# LPC8N04demoVB.net
KiCad netlist of a schematic drawn in Altium Designer
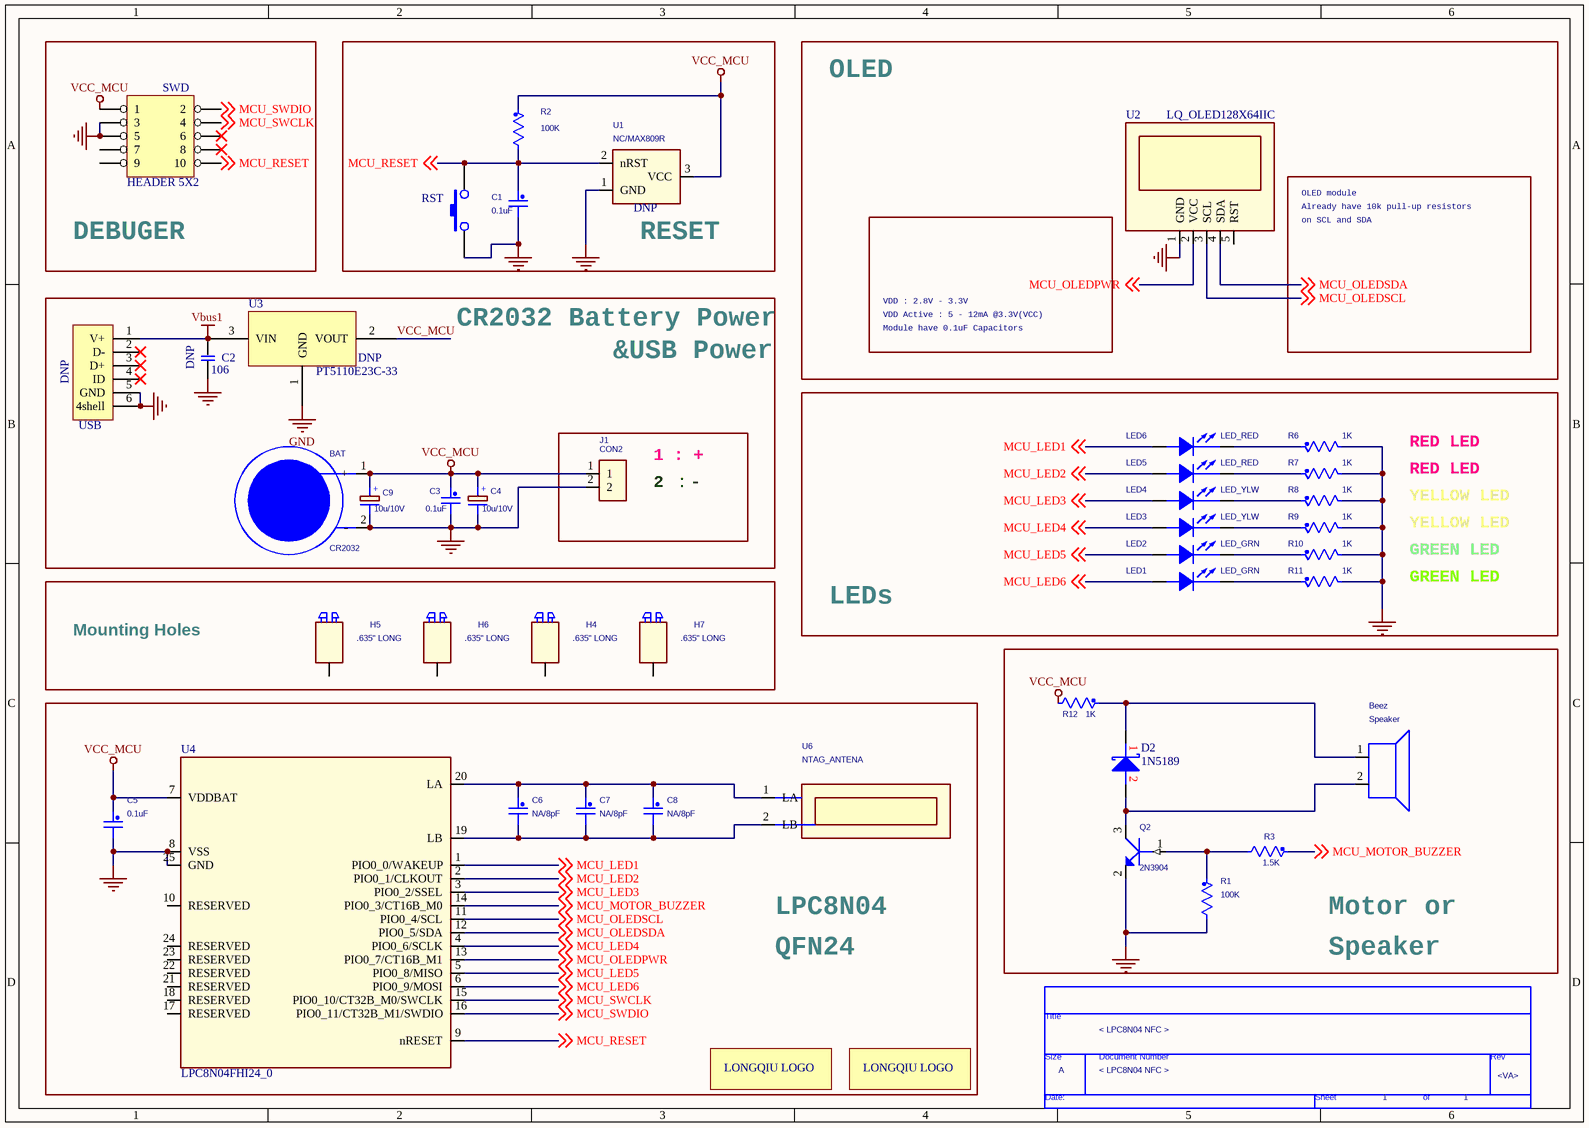
[diagram p0: LPC8N04demoVB.SchDoc]

(export (version "E")
  (design (tool "Eeschema 10.0.6"))
  (components
    (comp (ref "*")
      (value "TitleBlock0")
      (fields
        (field (name "DOC") "< LPC8N04 NFC >")
        (field (name "REVCODE") "<VA>")
        (field (name "TITLE") "< LPC8N04 NFC >")
        (field (name "PAGE SIZE") "A")
        (field (name "PAGE NUMBER") "1")
        (field (name "PAGE COUNT") "1")
      )
      (libsource (lib "*") (part "TitleBlock0"))
    )
    (comp (ref "BAT") (value "CR2032") (footprint "LQ_CR2032") (libsource (lib "*") (part "CR2032")))
    (comp (ref "Beez") (value "Speaker") (libsource (lib "*") (part "BUZZER_0")))
    (comp (ref "C1") (value "0.1uF") (footprint "LQ_C0603") (libsource (lib "*") (part "C_Generic")))
    (comp (ref "C2")
      (value "106")
      (footprint "LQ_C1206T")
      (description "CAP")
      (libsource (lib "*") (part "LQ_CAP"))
    )
    (comp (ref "C3") (value "0.1uF") (footprint "LQ_C0603") (libsource (lib "*") (part "C_Generic")))
    (comp (ref "C4") (value "10u/10V") (libsource (lib "*") (part "CAP PN")))
    (comp (ref "C5") (value "0.1uF") (footprint "LQ_C0603") (libsource (lib "*") (part "C_Generic")))
    (comp (ref "C6") (value "NA/8pF") (footprint "LQ_C0603") (libsource (lib "*") (part "C_Generic")))
    (comp (ref "C7") (value "NA/8pF") (footprint "LQ_C0603") (libsource (lib "*") (part "C_Generic")))
    (comp (ref "C8") (value "NA/8pF") (footprint "LQ_C0603") (libsource (lib "*") (part "C_Generic")))
    (comp (ref "C9") (value "10u/10V") (libsource (lib "*") (part "CAP PN")))
    (comp (ref "D2")
      (value "1N5189")
      (footprint "LQ_D1206Z")
      (description "Schottky Diode")
      (libsource (lib "chiusir") (part "LQ_Z"))
    )
    (comp (ref "H4")
      (value ".635\" LONG")
      (description "FASTENER, STANDOFF 4.5MMX3.53XM3.0X0.5 ROUND THR .635\"L BRASS")
      (libsource (lib "*") (part "SPACER"))
    )
    (comp (ref "H5")
      (value ".635\" LONG")
      (description "FASTENER, STANDOFF 4.5MMX3.53XM3.0X0.5 ROUND THR .635\"L BRASS")
      (libsource (lib "*") (part "SPACER"))
    )
    (comp (ref "H6")
      (value ".635\" LONG")
      (description "FASTENER, STANDOFF 4.5MMX3.53XM3.0X0.5 ROUND THR .635\"L BRASS")
      (libsource (lib "*") (part "SPACER"))
    )
    (comp (ref "H7")
      (value ".635\" LONG")
      (description "FASTENER, STANDOFF 4.5MMX3.53XM3.0X0.5 ROUND THR .635\"L BRASS")
      (libsource (lib "*") (part "SPACER"))
    )
    (comp (ref "J1") (value "CON2") (footprint "LQ_SIP2") (libsource (lib "*") (part "CON2")))
    (comp (ref "LED1") (value "LED_GRN") (libsource (lib "*") (part "LED_DIP_0")))
    (comp (ref "LED2") (value "LED_GRN") (libsource (lib "*") (part "LED_DIP_0")))
    (comp (ref "LED3") (value "LED_YLW") (libsource (lib "*") (part "LED_DIP_0")))
    (comp (ref "LED4") (value "LED_YLW") (libsource (lib "*") (part "LED_DIP_0")))
    (comp (ref "LED5") (value "LED_RED") (libsource (lib "*") (part "LED_DIP_0")))
    (comp (ref "LED6") (value "LED_RED") (libsource (lib "*") (part "LED_DIP_0")))
    (comp (ref "LQ") (value "LOGO") (footprint "LOGO5X8MM") (libsource (lib "chiusir") (part "LOGO")))
    (comp (ref "LQ1") (value "LOGO") (footprint "NXPlogo35X81mm") (libsource (lib "chiusir") (part "LOGO")))
    (comp (ref "Q2") (value "2N3904") (libsource (lib "*") (part "2N3904_0")))
    (comp (ref "R1") (value "100K") (footprint "LQ_R0603") (libsource (lib "*") (part "Register")))
    (comp (ref "R2") (value "100K") (libsource (lib "*") (part "R_Generic")))
    (comp (ref "R3") (value "1.5K") (footprint "LQ_R0603") (libsource (lib "*") (part "Register")))
    (comp (ref "R6") (value "1K") (footprint "LQ_R0603") (libsource (lib "*") (part "Register_Dup1")))
    (comp (ref "R7") (value "1K") (footprint "LQ_R0603") (libsource (lib "*") (part "Register_Dup1")))
    (comp (ref "R8") (value "1K") (footprint "LQ_R0603") (libsource (lib "*") (part "Register_Dup1")))
    (comp (ref "R9") (value "1K") (footprint "LQ_R0603") (libsource (lib "*") (part "Register_Dup1")))
    (comp (ref "R10") (value "1K") (footprint "LQ_R0603") (libsource (lib "*") (part "Register_Dup1")))
    (comp (ref "R11") (value "1K") (footprint "LQ_R0603") (libsource (lib "*") (part "Register_Dup1")))
    (comp (ref "R12") (value "1K") (footprint "LQ_R0603") (libsource (lib "*") (part "Register")))
    (comp (ref "RST") (value "SW-PB") (footprint "LQ_BT2SMT") (libsource (lib "*") (part "SW-PB")))
    (comp (ref "SWD")
      (value "HEADER 5X2")
      (footprint "LQ_JTAG5X2-1.27")
      (libsource (lib "*") (part "HEADER 5X2"))
    )
    (comp (ref "U1") (value "NC/MAX809R") (footprint "LQ_SOT-23NPN") (libsource (lib "*") (part "MAX809R")))
    (comp (ref "U2")
      (value "LQ_OLED128X64IIC")
      (footprint "LQ_OLED128x64IIC")
      (libsource (lib "LPC8N04_CLOCK_162_Library") (part "LQ_OLED128645IIC"))
    )
    (comp (ref "U3")
      (value "PT5110E23C-33")
      (footprint "LQ_SOT-23NPN")
      (libsource (lib "ForMyUse") (part "AMS1117"))
    )
    (comp (ref "U4")
      (value "LPC8N04FHI24_0")
      (footprint "LQ_HVQFN24")
      (libsource (lib "LPC8N04_CLOCK_162_Library") (part "LPC8N04FHI24_0"))
    )
    (comp (ref "U6")
      (value "NTAG_ANTENA")
      (footprint "NFCClass3Ant3T-2")
      (libsource (lib "*") (part "NTAG_ANTENA"))
    )
    (comp (ref "USB") (value "USB") (footprint "LQ_MICROUSB-5PIN") (libsource (lib "*") (part "MINIUSB")))
  )
  (nets
    (net (code "1") (name "GND") (class "Default")
      (node (ref "BAT") (pin "2") (pinfunction "-_2") (pintype "passive"))
      (node (ref "C1") (pin "2") (pinfunction "2_2") (pintype "passive"))
      (node (ref "C2") (pin "2") (pinfunction "2_2") (pintype "passive"))
      (node (ref "C3") (pin "2") (pinfunction "2_2") (pintype "passive"))
      (node (ref "C4") (pin "2") (pinfunction "2_2") (pintype "passive"))
      (node (ref "C5") (pin "2") (pinfunction "2_2") (pintype "passive"))
      (node (ref "C9") (pin "2") (pinfunction "2_2") (pintype "passive"))
      (node (ref "J1") (pin "2") (pinfunction "2_2") (pintype "passive"))
      (node (ref "Q2") (pin "2") (pinfunction "EMITTER_2") (pintype "passive"))
      (node (ref "R1") (pin "2") (pinfunction "2_2") (pintype "passive"))
      (node (ref "R10") (pin "2") (pinfunction "2_2") (pintype "passive"))
      (node (ref "R11") (pin "2") (pinfunction "2_2") (pintype "passive"))
      (node (ref "R6") (pin "2") (pinfunction "2_2") (pintype "passive"))
      (node (ref "R7") (pin "2") (pinfunction "2_2") (pintype "passive"))
      (node (ref "R8") (pin "2") (pinfunction "2_2") (pintype "passive"))
      (node (ref "R9") (pin "2") (pinfunction "2_2") (pintype "passive"))
      (node (ref "RST") (pin "1") (pinfunction "1_1") (pintype "passive"))
      (node (ref "SWD") (pin "3") (pinfunction "3_3") (pintype "passive"))
      (node (ref "SWD") (pin "5") (pinfunction "5_5") (pintype "passive"))
      (node (ref "U1") (pin "1") (pinfunction "GND_1") (pintype "passive"))
      (node (ref "U2") (pin "1") (pinfunction "GND_1") (pintype "passive"))
      (node (ref "U3") (pin "1") (pinfunction "GND_1") (pintype "power_in"))
      (node (ref "U4") (pin "25") (pinfunction "GND_25") (pintype "passive"))
      (node (ref "U4") (pin "8") (pinfunction "VSS_8") (pintype "passive"))
      (node (ref "USB") (pin "5") (pinfunction "GND_5") (pintype "passive"))
      (node (ref "USB") (pin "6") (pinfunction "4shell_6") (pintype "passive"))
    )
    (net (code "2") (name "MCU_LED1") (class "Default")
      (node (ref "LED6") (pin "1") (pinfunction "ANODE_1") (pintype "passive"))
      (node (ref "U4") (pin "1") (pinfunction "PIO0_0/WAKEUP_1") (pintype "passive"))
    )
    (net (code "3") (name "MCU_LED2") (class "Default")
      (node (ref "LED5") (pin "1") (pinfunction "ANODE_1") (pintype "passive"))
      (node (ref "U4") (pin "2") (pinfunction "PIO0_1/CLKOUT_2") (pintype "passive"))
    )
    (net (code "4") (name "MCU_LED3") (class "Default")
      (node (ref "LED4") (pin "1") (pinfunction "ANODE_1") (pintype "passive"))
      (node (ref "U4") (pin "3") (pinfunction "PIO0_2/SSEL_3") (pintype "passive"))
    )
    (net (code "5") (name "MCU_LED4") (class "Default")
      (node (ref "LED3") (pin "1") (pinfunction "ANODE_1") (pintype "passive"))
      (node (ref "U4") (pin "4") (pinfunction "PIO0_6/SCLK_4") (pintype "passive"))
    )
    (net (code "6") (name "MCU_LED5") (class "Default")
      (node (ref "LED2") (pin "1") (pinfunction "ANODE_1") (pintype "passive"))
      (node (ref "U4") (pin "5") (pinfunction "PIO0_8/MISO_5") (pintype "passive"))
    )
    (net (code "7") (name "MCU_LED6") (class "Default")
      (node (ref "LED1") (pin "1") (pinfunction "ANODE_1") (pintype "passive"))
      (node (ref "U4") (pin "6") (pinfunction "PIO0_9/MOSI_6") (pintype "passive"))
    )
    (net (code "8") (name "MCU_MOTOR_BUZZER") (class "Default")
      (node (ref "R3") (pin "1") (pinfunction "1_1") (pintype "passive"))
      (node (ref "U4") (pin "14") (pinfunction "PIO0_3/CT16B_M0_14") (pintype "passive"))
    )
    (net (code "9") (name "MCU_OLEDPWR") (class "Default")
      (node (ref "U2") (pin "2") (pinfunction "VCC_2") (pintype "passive"))
      (node (ref "U4") (pin "13") (pinfunction "PIO0_7/CT16B_M1_13") (pintype "passive"))
    )
    (net (code "10") (name "MCU_OLEDSCL") (class "Default")
      (node (ref "U2") (pin "3") (pinfunction "SCL_3") (pintype "passive"))
      (node (ref "U4") (pin "11") (pinfunction "PIO0_4/SCL_11") (pintype "passive"))
    )
    (net (code "11") (name "MCU_OLEDSDA") (class "Default")
      (node (ref "U2") (pin "4") (pinfunction "SDA_4") (pintype "passive"))
      (node (ref "U4") (pin "12") (pinfunction "PIO0_5/SDA_12") (pintype "passive"))
    )
    (net (code "12") (name "MCU_RESET") (class "Default")
      (node (ref "C1") (pin "1") (pinfunction "1_1") (pintype "passive"))
      (node (ref "R2") (pin "2") (pinfunction "2_2") (pintype "passive"))
      (node (ref "RST") (pin "2") (pinfunction "2_2") (pintype "passive"))
      (node (ref "SWD") (pin "10") (pinfunction "10_10") (pintype "passive"))
      (node (ref "U1") (pin "2") (pinfunction "nRST_2") (pintype "passive"))
      (node (ref "U4") (pin "9") (pinfunction "nRESET_9") (pintype "passive"))
    )
    (net (code "13") (name "MCU_SWCLK") (class "Default")
      (node (ref "SWD") (pin "4") (pinfunction "4_4") (pintype "passive"))
      (node (ref "U4") (pin "15") (pinfunction "PIO0_10/CT32B_M0/SWCLK_15") (pintype "passive"))
    )
    (net (code "14") (name "MCU_SWDIO") (class "Default")
      (node (ref "SWD") (pin "2") (pinfunction "2_2") (pintype "passive"))
      (node (ref "U4") (pin "16") (pinfunction "PIO0_11/CT32B_M1/SWDIO_16") (pintype "passive"))
    )
    (net (code "15") (name "Net-(Beez-A)") (class "Default")
      (node (ref "Beez") (pin "1") (pinfunction "A_1") (pintype "passive"))
      (node (ref "D2") (pin "1") (pinfunction "1_1") (pintype "passive"))
      (node (ref "R12") (pin "1") (pinfunction "1_1") (pintype "passive"))
    )
    (net (code "16") (name "Net-(Beez-B)") (class "Default")
      (node (ref "Beez") (pin "2") (pinfunction "B_2") (pintype "passive"))
      (node (ref "D2") (pin "2") (pinfunction "2_2") (pintype "passive"))
      (node (ref "Q2") (pin "3") (pinfunction "COLLECTOR_3") (pintype "passive"))
    )
    (net (code "17") (name "Net-(LED1-CATHODE)") (class "Default")
      (node (ref "LED1") (pin "2") (pinfunction "CATHODE_2") (pintype "passive"))
      (node (ref "R11") (pin "1") (pinfunction "1_1") (pintype "passive"))
    )
    (net (code "18") (name "Net-(LED2-CATHODE)") (class "Default")
      (node (ref "LED2") (pin "2") (pinfunction "CATHODE_2") (pintype "passive"))
      (node (ref "R10") (pin "1") (pinfunction "1_1") (pintype "passive"))
    )
    (net (code "19") (name "Net-(LED3-CATHODE)") (class "Default")
      (node (ref "LED3") (pin "2") (pinfunction "CATHODE_2") (pintype "passive"))
      (node (ref "R9") (pin "1") (pinfunction "1_1") (pintype "passive"))
    )
    (net (code "20") (name "Net-(LED4-CATHODE)") (class "Default")
      (node (ref "LED4") (pin "2") (pinfunction "CATHODE_2") (pintype "passive"))
      (node (ref "R8") (pin "1") (pinfunction "1_1") (pintype "passive"))
    )
    (net (code "21") (name "Net-(LED5-CATHODE)") (class "Default")
      (node (ref "LED5") (pin "2") (pinfunction "CATHODE_2") (pintype "passive"))
      (node (ref "R7") (pin "1") (pinfunction "1_1") (pintype "passive"))
    )
    (net (code "22") (name "Net-(LED6-CATHODE)") (class "Default")
      (node (ref "LED6") (pin "2") (pinfunction "CATHODE_2") (pintype "passive"))
      (node (ref "R6") (pin "1") (pinfunction "1_1") (pintype "passive"))
    )
    (net (code "23") (name "Net-(Q2-BASE)") (class "Default")
      (node (ref "Q2") (pin "1") (pinfunction "BASE_1") (pintype "input"))
      (node (ref "R1") (pin "1") (pinfunction "1_1") (pintype "passive"))
      (node (ref "R3") (pin "2") (pinfunction "2_2") (pintype "passive"))
    )
    (net (code "24") (name "Net-(U4-LA)") (class "Default")
      (node (ref "C6") (pin "1") (pinfunction "1_1") (pintype "passive"))
      (node (ref "C7") (pin "1") (pinfunction "1_1") (pintype "passive"))
      (node (ref "C8") (pin "1") (pinfunction "1_1") (pintype "passive"))
      (node (ref "U4") (pin "20") (pinfunction "LA_20") (pintype "passive"))
      (node (ref "U6") (pin "1") (pinfunction "LA_1") (pintype "passive"))
    )
    (net (code "25") (name "Net-(U4-LB)") (class "Default")
      (node (ref "C6") (pin "2") (pinfunction "2_2") (pintype "passive"))
      (node (ref "C7") (pin "2") (pinfunction "2_2") (pintype "passive"))
      (node (ref "C8") (pin "2") (pinfunction "2_2") (pintype "passive"))
      (node (ref "U4") (pin "19") (pinfunction "LB_19") (pintype "passive"))
      (node (ref "U6") (pin "2") (pinfunction "LB_2") (pintype "passive"))
    )
    (net (code "26") (name "VCC_MCU") (class "Default")
      (node (ref "BAT") (pin "1") (pinfunction "+_1") (pintype "passive"))
      (node (ref "C3") (pin "1") (pinfunction "1_1") (pintype "passive"))
      (node (ref "C4") (pin "1") (pinfunction "1_1") (pintype "passive"))
      (node (ref "C5") (pin "1") (pinfunction "1_1") (pintype "passive"))
      (node (ref "C9") (pin "1") (pinfunction "1_1") (pintype "passive"))
      (node (ref "J1") (pin "1") (pinfunction "1_1") (pintype "passive"))
      (node (ref "R12") (pin "2") (pinfunction "2_2") (pintype "passive"))
      (node (ref "R2") (pin "1") (pinfunction "1_1") (pintype "passive"))
      (node (ref "SWD") (pin "1") (pinfunction "1_1") (pintype "passive"))
      (node (ref "U1") (pin "3") (pinfunction "VCC_3") (pintype "passive"))
      (node (ref "U3") (pin "2") (pinfunction "VOUT_2") (pintype "power_in"))
      (node (ref "U4") (pin "7") (pinfunction "VDDBAT_7") (pintype "passive"))
    )
    (net (code "27") (name "Vbus1") (class "Default")
      (node (ref "C2") (pin "1") (pinfunction "1_1") (pintype "passive"))
      (node (ref "U3") (pin "3") (pinfunction "VIN_3") (pintype "power_in"))
      (node (ref "USB") (pin "1") (pinfunction "V+_1") (pintype "passive"))
    )
    (net (code "28") (name "unconnected-(H4-NC_1-Pad1)") (class "Default")
      (node (ref "H4") (pin "1") (pinfunction "NC_1_1") (pintype "passive"))
    )
    (net (code "29") (name "unconnected-(H5-NC_1-Pad1)") (class "Default")
      (node (ref "H5") (pin "1") (pinfunction "NC_1_1") (pintype "passive"))
    )
    (net (code "30") (name "unconnected-(H6-NC_1-Pad1)") (class "Default")
      (node (ref "H6") (pin "1") (pinfunction "NC_1_1") (pintype "passive"))
    )
    (net (code "31") (name "unconnected-(H7-NC_1-Pad1)") (class "Default")
      (node (ref "H7") (pin "1") (pinfunction "NC_1_1") (pintype "passive"))
    )
    (net (code "32") (name "unconnected-(SWD-Pad6)") (class "Default")
      (node (ref "SWD") (pin "6") (pinfunction "6_6") (pintype "passive+no_connect"))
    )
    (net (code "33") (name "unconnected-(SWD-Pad7)") (class "Default")
      (node (ref "SWD") (pin "7") (pinfunction "7_7") (pintype "passive"))
    )
    (net (code "34") (name "unconnected-(SWD-Pad8)") (class "Default")
      (node (ref "SWD") (pin "8") (pinfunction "8_8") (pintype "passive+no_connect"))
    )
    (net (code "35") (name "unconnected-(SWD-Pad9)") (class "Default")
      (node (ref "SWD") (pin "9") (pinfunction "9_9") (pintype "passive"))
    )
    (net (code "36") (name "unconnected-(U2-RST-Pad5)") (class "Default")
      (node (ref "U2") (pin "5") (pinfunction "RST_5") (pintype "passive"))
    )
    (net (code "37") (name "unconnected-(U4-RESERVED-Pad10)") (class "Default")
      (node (ref "U4") (pin "10") (pinfunction "RESERVED_10") (pintype "passive"))
    )
    (net (code "38") (name "unconnected-(U4-RESERVED-Pad17)") (class "Default")
      (node (ref "U4") (pin "17") (pinfunction "RESERVED_17") (pintype "passive"))
    )
    (net (code "39") (name "unconnected-(U4-RESERVED-Pad18)") (class "Default")
      (node (ref "U4") (pin "18") (pinfunction "RESERVED_18") (pintype "passive"))
    )
    (net (code "40") (name "unconnected-(U4-RESERVED-Pad21)") (class "Default")
      (node (ref "U4") (pin "21") (pinfunction "RESERVED_21") (pintype "passive"))
    )
    (net (code "41") (name "unconnected-(U4-RESERVED-Pad22)") (class "Default")
      (node (ref "U4") (pin "22") (pinfunction "RESERVED_22") (pintype "passive"))
    )
    (net (code "42") (name "unconnected-(U4-RESERVED-Pad23)") (class "Default")
      (node (ref "U4") (pin "23") (pinfunction "RESERVED_23") (pintype "passive"))
    )
    (net (code "43") (name "unconnected-(U4-RESERVED-Pad24)") (class "Default")
      (node (ref "U4") (pin "24") (pinfunction "RESERVED_24") (pintype "passive"))
    )
    (net (code "44") (name "unconnected-(USB-D+-Pad3)") (class "Default")
      (node (ref "USB") (pin "3") (pinfunction "D+_3") (pintype "passive+no_connect"))
    )
    (net (code "45") (name "unconnected-(USB-D--Pad2)") (class "Default")
      (node (ref "USB") (pin "2") (pinfunction "D-_2") (pintype "passive+no_connect"))
    )
    (net (code "46") (name "unconnected-(USB-ID-Pad4)") (class "Default")
      (node (ref "USB") (pin "4") (pinfunction "ID_4") (pintype "passive+no_connect"))
    )
  )
)
